# Sensor_Board.net
KiCad netlist of a schematic drawn in Altium Designer
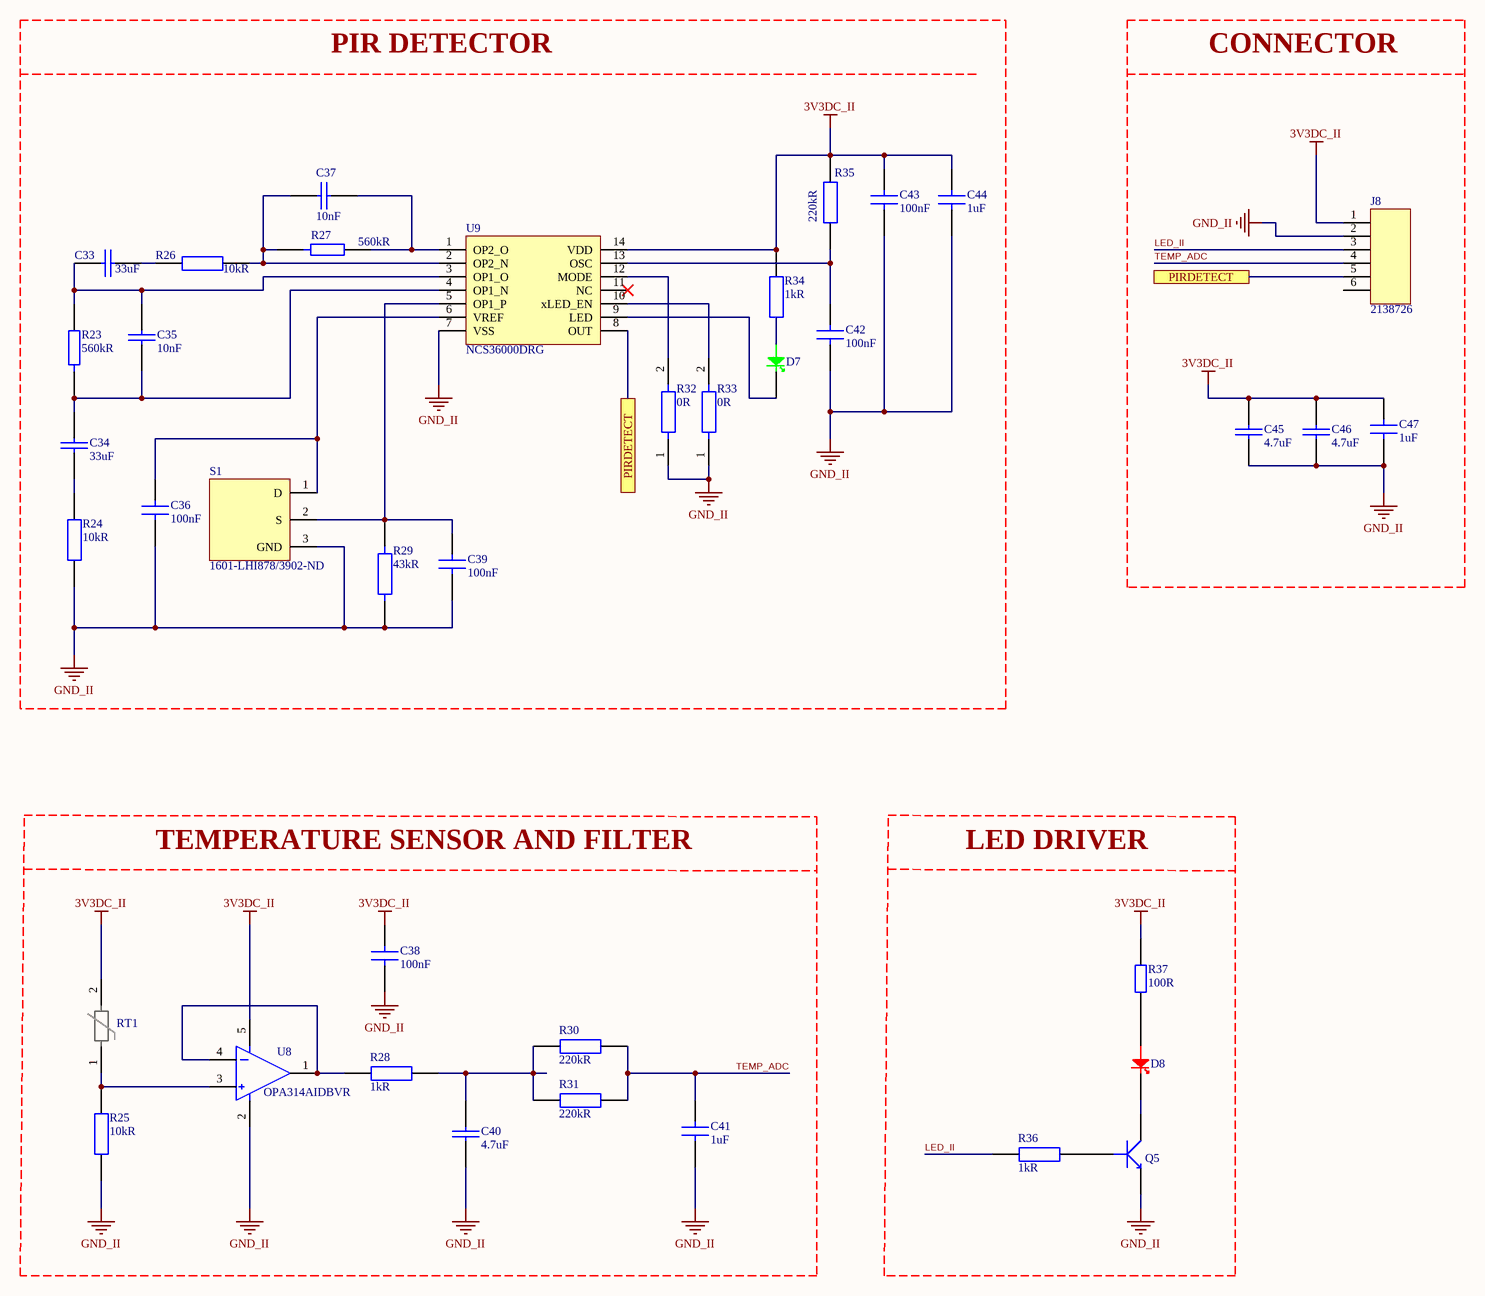
[diagram p0: Sensor Board.SchDoc]

(export (version "E")
  (design (tool "Eeschema 10.0.6"))
  (components
    (comp (ref "C33")
      (value "C3216X5R1E336M160AC")
      (footprint "CAP_1206")
      (description "Cap Ceramic 33uF 25V X5R 20% SMD 1206 85C T/R")
      (fields
        (field (name "MANUFACTURER") "TDK")
        (field (name "TOLERANCE") "20%")
        (field (name "CAPACITANCE") "33uF")
      )
      (libsource (lib "SecurityBoard") (part "CAP CER 33uF 1206"))
    )
    (comp (ref "C34")
      (value "C3216X5R1E336M160AC")
      (footprint "CAP_1206")
      (description "Cap Ceramic 33uF 25V X5R 20% SMD 1206 85C T/R")
      (fields
        (field (name "MANUFACTURER") "TDK")
        (field (name "TOLERANCE") "20%")
        (field (name "CAPACITANCE") "33uF")
      )
      (libsource (lib "SecurityBoard") (part "CAP CER 33uF 1206"))
    )
    (comp (ref "C35")
      (value "0603B103K160CT")
      (footprint "cap_0603")
      (fields
        (field (name "MANUFACTURER") "Walsin Technologies")
        (field (name "TOLERANCE") "10%")
        (field (name "CAPACITANCE") "10nF")
      )
      (libsource (lib "SecurityBoard") (part "CAP CER 10nF 0603"))
    )
    (comp (ref "C36")
      (value "C0603X104K4RACTU")
      (footprint "cap_0603")
      (description "CAP CER 0.1UF 16V X7R 0603")
      (fields
        (field (name "MANUFACTURER") "KEMET")
        (field (name "TOLERANCE") "10%")
        (field (name "CAPACITANCE") "100nF")
        (field (name "DESIGNEDBY") "ENES")
      )
      (libsource (lib "SecurityBoard") (part "CAP CER 100nF  0603"))
    )
    (comp (ref "C37")
      (value "0603B103K160CT")
      (footprint "cap_0603")
      (fields
        (field (name "MANUFACTURER") "Walsin Technologies")
        (field (name "TOLERANCE") "10%")
        (field (name "CAPACITANCE") "10nF")
      )
      (libsource (lib "SecurityBoard") (part "CAP CER 10nF 0603"))
    )
    (comp (ref "C38")
      (value "C0603X104K4RACTU")
      (footprint "cap_0603")
      (description "CAP CER 0.1UF 16V X7R 0603")
      (fields
        (field (name "MANUFACTURER") "KEMET")
        (field (name "TOLERANCE") "10%")
        (field (name "CAPACITANCE") "100nF")
        (field (name "DESIGNEDBY") "ENES")
      )
      (libsource (lib "SecurityBoard") (part "CAP CER 100nF  0603"))
    )
    (comp (ref "C39")
      (value "C0603X104K4RACTU")
      (footprint "cap_0603")
      (description "CAP CER 0.1UF 16V X7R 0603")
      (fields
        (field (name "MANUFACTURER") "KEMET")
        (field (name "TOLERANCE") "10%")
        (field (name "CAPACITANCE") "100nF")
        (field (name "DESIGNEDBY") "ENES")
      )
      (libsource (lib "SecurityBoard") (part "CAP CER 100nF  0603"))
    )
    (comp (ref "C40")
      (value "CL21A475KAQNNNE")
      (footprint "CAP_0805")
      (description "CAP CER 4.7uF %10 0805")
      (fields
        (field (name "MANUFACTURER") "Samsung")
        (field (name "TOLERANCE") "10%")
        (field (name "CAPACITANCE") "4.7uF")
      )
      (libsource (lib "SecurityBoard") (part "CAP CER 4.7uF 0805"))
    )
    (comp (ref "C41")
      (value "CL21B105KBFNNNE")
      (footprint "CAP_0805")
      (fields
        (field (name "MANUFACTURER") "Samsung")
        (field (name "TOLERANCE") "10%")
        (field (name "VOLTAGE") "50V")
        (field (name "CAPACITANCE") "1uF")
      )
      (libsource (lib "SecurityBoard") (part "CAP CER 1uF 0805"))
    )
    (comp (ref "C42")
      (value "C0603X104K4RACTU")
      (footprint "cap_0603")
      (description "CAP CER 0.1UF 16V X7R 0603")
      (fields
        (field (name "MANUFACTURER") "KEMET")
        (field (name "TOLERANCE") "10%")
        (field (name "CAPACITANCE") "100nF")
        (field (name "DESIGNEDBY") "ENES")
      )
      (libsource (lib "SecurityBoard") (part "CAP CER 100nF  0603"))
    )
    (comp (ref "C43")
      (value "C0603X104K4RACTU")
      (footprint "cap_0603")
      (description "CAP CER 0.1UF 16V X7R 0603")
      (fields
        (field (name "MANUFACTURER") "KEMET")
        (field (name "TOLERANCE") "10%")
        (field (name "CAPACITANCE") "100nF")
        (field (name "DESIGNEDBY") "ENES")
      )
      (libsource (lib "SecurityBoard") (part "CAP CER 100nF  0603"))
    )
    (comp (ref "C44")
      (value "CL21B105KBFNNNE")
      (footprint "CAP_0805")
      (fields
        (field (name "MANUFACTURER") "Samsung")
        (field (name "TOLERANCE") "10%")
        (field (name "VOLTAGE") "50V")
        (field (name "CAPACITANCE") "1uF")
      )
      (libsource (lib "SecurityBoard") (part "CAP CER 1uF 0805"))
    )
    (comp (ref "C45")
      (value "CL21A475KAQNNNE")
      (footprint "CAP_0805")
      (description "CAP CER 4.7uF %10 0805")
      (fields
        (field (name "MANUFACTURER") "Samsung")
        (field (name "TOLERANCE") "10%")
        (field (name "CAPACITANCE") "4.7uF")
      )
      (libsource (lib "SecurityBoard") (part "CAP CER 4.7uF 0805"))
    )
    (comp (ref "C46")
      (value "CL21A475KAQNNNE")
      (footprint "CAP_0805")
      (description "CAP CER 4.7uF %10 0805")
      (fields
        (field (name "MANUFACTURER") "Samsung")
        (field (name "TOLERANCE") "10%")
        (field (name "CAPACITANCE") "4.7uF")
      )
      (libsource (lib "SecurityBoard") (part "CAP CER 4.7uF 0805"))
    )
    (comp (ref "C47")
      (value "CL21B105KBFNNNE")
      (footprint "CAP_0805")
      (fields
        (field (name "MANUFACTURER") "Samsung")
        (field (name "TOLERANCE") "10%")
        (field (name "VOLTAGE") "50V")
        (field (name "CAPACITANCE") "1uF")
      )
      (libsource (lib "SecurityBoard") (part "CAP CER 1uF 0805"))
    )
    (comp (ref "D7")
      (value "APT1608ZGCK")
      (footprint "LED_GR_0805")
      (description "Green 1.6 x 0.8 mm 120° 350 mcd Clear 3.3 V Surface Mount Chip LED Lamp")
      (fields (field (name "MANUFACTURER") "Kingbright"))
      (libsource (lib "SecurityBoard") (part "LED GREEN 0805"))
    )
    (comp (ref "D8")
      (value "LTST-C171EKT")
      (footprint "LED_RED_0805")
      (description "LED RED CLEAR 0805 SMD")
      (fields (field (name "MANUFACTURER") "Vishay Lite-On"))
      (libsource (lib "SecurityBoard") (part "LED RED 0805"))
    )
    (comp (ref "J8")
      (value "64800611622")
      (footprint "64800611622")
      (fields
        (field (name "MANUFACTURER") "Wurth Electronics")
        (field (name "SUPPLIER PART NUMBER 1") "2138726")
      )
      (libsource (lib "SecurityBoard") (part "64800611622_conn_6pin"))
    )
    (comp (ref "Q5")
      (value "MMBT3904-7-F")
      (footprint "MMBT3904-7-F")
      (description "Transistor General Purpose BJT NPN 40 Volt 0.2A Automotive 3-Pin SOT-23")
      (fields (field (name "MANUFACTURER") "Diodes Zetex"))
      (libsource (lib "SecurityBoard") (part "MMBT3904-7-F"))
    )
    (comp (ref "R23")
      (value "RC0603JR-07560KL")
      (footprint "res_0603")
      (description "RES SMD 560K OHM 5% 1/10W 0603")
      (fields
        (field (name "MANUFACTURER") "Yageo")
        (field (name "TOLERANCE") "5%")
        (field (name "RESISTANCE") "560kR")
      )
      (libsource (lib "SecurityBoard") (part "RES 560K OHM 0603"))
    )
    (comp (ref "R24")
      (value "RC0603FR-0710KL")
      (footprint "res_0603")
      (description "Res General Purpose Thick Film 0603 10K Ohm 1% 1/10W ±100ppm/°C Molded SMD Paper T/R")
      (fields
        (field (name "MANUFACTURER") "Yageo")
        (field (name "TOLERANCE") "1%")
        (field (name "RESISTANCE") "10kR")
      )
      (libsource (lib "SecurityBoard") (part "RES 10K OHM 0603"))
    )
    (comp (ref "R25")
      (value "RC0603FR-0710KL")
      (footprint "res_0603")
      (description "Res General Purpose Thick Film 0603 10K Ohm 1% 1/10W ±100ppm/°C Molded SMD Paper T/R")
      (fields
        (field (name "MANUFACTURER") "Yageo")
        (field (name "TOLERANCE") "1%")
        (field (name "RESISTANCE") "10kR")
      )
      (libsource (lib "SecurityBoard") (part "RES 10K OHM 0603"))
    )
    (comp (ref "R26")
      (value "RC0603FR-0710KL")
      (footprint "res_0603")
      (description "Res General Purpose Thick Film 0603 10K Ohm 1% 1/10W ±100ppm/°C Molded SMD Paper T/R")
      (fields
        (field (name "MANUFACTURER") "Yageo")
        (field (name "TOLERANCE") "1%")
        (field (name "RESISTANCE") "10kR")
      )
      (libsource (lib "SecurityBoard") (part "RES 10K OHM 0603"))
    )
    (comp (ref "R27")
      (value "RC0603JR-07560KL")
      (footprint "res_0603")
      (description "RES SMD 560K OHM 5% 1/10W 0603")
      (fields
        (field (name "MANUFACTURER") "Yageo")
        (field (name "TOLERANCE") "5%")
        (field (name "RESISTANCE") "560kR")
      )
      (libsource (lib "SecurityBoard") (part "RES 560K OHM 0603"))
    )
    (comp (ref "R28")
      (value "AC0603FR-071KL")
      (footprint "res_0603")
      (description "Res Thick Film 0603 1K Ohm 1% 0.1W(1/10W) ±100ppm/C Epoxy Pad SMD Automotive T/R")
      (fields
        (field (name "MANUFACTURER") "Yageo")
        (field (name "TOLERANCE") "1%")
        (field (name "RESISTANCE") "1kR")
      )
      (libsource (lib "SecurityBoard") (part "RES 1K OHM 0603"))
    )
    (comp (ref "R29")
      (value "RC0603DR-0743KL")
      (footprint "res_0603")
      (description "General Purpose Chip Resistor Thick Film 0603 43kOhm 0.5% Paper T/R")
      (fields
        (field (name "MANUFACTURER") "Yageo")
        (field (name "TOLERANCE") "0.5%")
        (field (name "RESISTANCE") "43kR")
      )
      (libsource (lib "SecurityBoard") (part "RES 43K OHM 0603"))
    )
    (comp (ref "R30")
      (value "RT0603BRD07220KL")
      (footprint "res_0603")
      (description "Thin Film Resistors - SMD 1/10W 220K ohm .1% 25ppm")
      (fields
        (field (name "MANUFACTURER") "Yageo")
        (field (name "TOLERANCE") "0.1%")
        (field (name "RESISTANCE") "220kR")
      )
      (libsource (lib "SecurityBoard") (part "RES 220K OHM 0603"))
    )
    (comp (ref "R31")
      (value "RT0603BRD07220KL")
      (footprint "res_0603")
      (description "Thin Film Resistors - SMD 1/10W 220K ohm .1% 25ppm")
      (fields
        (field (name "MANUFACTURER") "Yageo")
        (field (name "TOLERANCE") "0.1%")
        (field (name "RESISTANCE") "220kR")
      )
      (libsource (lib "SecurityBoard") (part "RES 220K OHM 0603"))
    )
    (comp (ref "R32")
      (value "RC0603JR-070RL")
      (footprint "res_0603")
      (description "RES SMD 0 OHM JUMPER 1/10W 0603")
      (fields
        (field (name "MANUFACTURER") "Yageo")
        (field (name "TOLERANCE") "1%")
        (field (name "RESISTANCE") "0R")
      )
      (libsource (lib "SecurityBoard") (part "RES 0 OHM 0603"))
    )
    (comp (ref "R33")
      (value "RC0603JR-070RL")
      (footprint "res_0603")
      (description "RES SMD 0 OHM JUMPER 1/10W 0603")
      (fields
        (field (name "MANUFACTURER") "Yageo")
        (field (name "TOLERANCE") "1%")
        (field (name "RESISTANCE") "0R")
      )
      (libsource (lib "SecurityBoard") (part "RES 0 OHM 0603"))
    )
    (comp (ref "R34")
      (value "AC0603FR-071KL")
      (footprint "res_0603")
      (description "Res Thick Film 0603 1K Ohm 1% 0.1W(1/10W) ±100ppm/C Epoxy Pad SMD Automotive T/R")
      (fields
        (field (name "MANUFACTURER") "Yageo")
        (field (name "TOLERANCE") "1%")
        (field (name "RESISTANCE") "1kR")
      )
      (libsource (lib "SecurityBoard") (part "RES 1K OHM 0603"))
    )
    (comp (ref "R35")
      (value "RT0603BRD07220KL")
      (footprint "res_0603")
      (description "Thin Film Resistors - SMD 1/10W 220K ohm .1% 25ppm")
      (fields
        (field (name "MANUFACTURER") "Yageo")
        (field (name "TOLERANCE") "0.1%")
        (field (name "RESISTANCE") "220kR")
      )
      (libsource (lib "SecurityBoard") (part "RES 220K OHM 0603"))
    )
    (comp (ref "R36")
      (value "AC0603FR-071KL")
      (footprint "res_0603")
      (description "Res Thick Film 0603 1K Ohm 1% 0.1W(1/10W) ±100ppm/C Epoxy Pad SMD Automotive T/R")
      (fields
        (field (name "MANUFACTURER") "Yageo")
        (field (name "TOLERANCE") "1%")
        (field (name "RESISTANCE") "1kR")
      )
      (libsource (lib "SecurityBoard") (part "RES 1K OHM 0603"))
    )
    (comp (ref "R37")
      (value "RE0603DRE07100RL")
      (footprint "res_0603")
      (description "Chip Resistor Precision Grade Thick Film 0603 100Ohm 0.5% Paper T/R")
      (fields
        (field (name "MANUFACTURER") "Yageo")
        (field (name "TOLERANCE") "0.5%")
        (field (name "RESISTANCE") "100R")
      )
      (libsource (lib "SecurityBoard") (part "RES 100 OHM 0603"))
    )
    (comp (ref "RT1")
      (value "TFPT1206L1002FM")
      (footprint "TFPT1206L1002FM")
      (description "Thermistor PTC 10K Ohm 1% 2-Pin 1206 Surface Mount Solder Pad T/R Automotive")
      (fields (field (name "MANUFACTURER") "Vishay Dale") (field (name "TOLERANCE") "1%"))
      (libsource (lib "SecurityBoard") (part "TFPT1206L1002FM"))
    )
    (comp (ref "S1")
      (value "1601-LHI878/3902-ND")
      (footprint "LHI 878/3902")
      (description "Sensor Pyro Detector Dual Motion")
      (fields
        (field (name "MANUFACTURER") "Excelitas Technology")
        (field (name "MANUFACTURER PART NUMBER") "LHI 878/3902")
        (field (name "DESIGNEDBY") "ENES")
      )
      (libsource (lib "SecurityBoard") (part "LHI 878/3902"))
    )
    (comp (ref "U8")
      (value "OPA314AIDBVR")
      (footprint "SOT23-5")
      (description "Op Amp OPA314AIDBVR")
      (fields (field (name "MANUFACTURER") "Texas Instruments"))
      (libsource (lib "SecurityBoard") (part "OPA314"))
    )
    (comp (ref "U9")
      (value "NCS36000DRG")
      (footprint "SOIC14")
      (description "Low Noise Amplifiers and LDO Regulator 14-Pin SOIC N T/R")
      (fields (field (name "MANUFACTURER") "ON Semiconductor"))
      (libsource (lib "SecurityBoard") (part "NCS36000DRG"))
    )
  )
  (nets
    (net (code "1") (name "/LED_II") (class "Default")
      (node (ref "J8") (pin "3") (pinfunction "3_3") (pintype "passive"))
      (node (ref "R36") (pin "1") (pinfunction "1_1") (pintype "passive"))
    )
    (net (code "2") (name "/PIRDETECT") (class "Default")
      (node (ref "J8") (pin "5") (pinfunction "5_5") (pintype "passive"))
      (node (ref "U9") (pin "8") (pinfunction "OUT_8") (pintype "passive"))
    )
    (net (code "3") (name "/TEMP_ADC") (class "Default")
      (node (ref "C41") (pin "2") (pinfunction "2_2") (pintype "passive"))
      (node (ref "J8") (pin "4") (pinfunction "4_4") (pintype "passive"))
      (node (ref "R30") (pin "2") (pinfunction "2_2") (pintype "passive"))
      (node (ref "R31") (pin "2") (pinfunction "2_2") (pintype "passive"))
    )
    (net (code "4") (name "3V3DC_II") (class "Default")
      (node (ref "C38") (pin "2") (pinfunction "2_2") (pintype "passive"))
      (node (ref "C43") (pin "2") (pinfunction "2_2") (pintype "passive"))
      (node (ref "C44") (pin "2") (pinfunction "2_2") (pintype "passive"))
      (node (ref "C45") (pin "2") (pinfunction "2_2") (pintype "passive"))
      (node (ref "C46") (pin "2") (pinfunction "2_2") (pintype "passive"))
      (node (ref "C47") (pin "2") (pinfunction "2_2") (pintype "passive"))
      (node (ref "J8") (pin "1") (pinfunction "1_1") (pintype "passive"))
      (node (ref "R34") (pin "2") (pinfunction "2_2") (pintype "passive"))
      (node (ref "R35") (pin "2") (pinfunction "2_2") (pintype "passive"))
      (node (ref "R37") (pin "2") (pinfunction "2_2") (pintype "passive"))
      (node (ref "RT1") (pin "2") (pinfunction "2_2") (pintype "passive"))
      (node (ref "U8") (pin "5") (pinfunction "5_5") (pintype "passive"))
      (node (ref "U9") (pin "14") (pinfunction "VDD_14") (pintype "passive"))
    )
    (net (code "5") (name "GND_II") (class "Default")
      (node (ref "C36") (pin "1") (pinfunction "1_1") (pintype "passive"))
      (node (ref "C38") (pin "1") (pinfunction "1_1") (pintype "passive"))
      (node (ref "C39") (pin "1") (pinfunction "1_1") (pintype "passive"))
      (node (ref "C40") (pin "1") (pinfunction "1_1") (pintype "passive"))
      (node (ref "C41") (pin "1") (pinfunction "1_1") (pintype "passive"))
      (node (ref "C42") (pin "1") (pinfunction "1_1") (pintype "passive"))
      (node (ref "C43") (pin "1") (pinfunction "1_1") (pintype "passive"))
      (node (ref "C44") (pin "1") (pinfunction "1_1") (pintype "passive"))
      (node (ref "C45") (pin "1") (pinfunction "1_1") (pintype "passive"))
      (node (ref "C46") (pin "1") (pinfunction "1_1") (pintype "passive"))
      (node (ref "C47") (pin "1") (pinfunction "1_1") (pintype "passive"))
      (node (ref "J8") (pin "2") (pinfunction "2_2") (pintype "passive"))
      (node (ref "Q5") (pin "E") (pinfunction "E_E") (pintype "passive"))
      (node (ref "R24") (pin "1") (pinfunction "1_1") (pintype "passive"))
      (node (ref "R25") (pin "1") (pinfunction "1_1") (pintype "passive"))
      (node (ref "R29") (pin "1") (pinfunction "_1_1") (pintype "passive"))
      (node (ref "R32") (pin "1") (pinfunction "_1_1") (pintype "passive"))
      (node (ref "R33") (pin "1") (pinfunction "_1_1") (pintype "passive"))
      (node (ref "S1") (pin "3") (pinfunction "GND_3") (pintype "passive"))
      (node (ref "U8") (pin "2") (pinfunction "2_2") (pintype "passive"))
      (node (ref "U9") (pin "7") (pinfunction "VSS_7") (pintype "passive"))
    )
    (net (code "6") (name "Net-(C33-Pad2)") (class "Default")
      (node (ref "C33") (pin "2") (pinfunction "2_2") (pintype "passive"))
      (node (ref "R26") (pin "1") (pinfunction "1_1") (pintype "passive"))
    )
    (net (code "7") (name "Net-(C34-Pad1)") (class "Default")
      (node (ref "C34") (pin "1") (pinfunction "1_1") (pintype "passive"))
      (node (ref "R24") (pin "2") (pinfunction "2_2") (pintype "passive"))
    )
    (net (code "8") (name "Net-(C40-Pad2)") (class "Default")
      (node (ref "C40") (pin "2") (pinfunction "2_2") (pintype "passive"))
      (node (ref "R28") (pin "2") (pinfunction "2_2") (pintype "passive"))
      (node (ref "R30") (pin "1") (pinfunction "1_1") (pintype "passive"))
      (node (ref "R31") (pin "1") (pinfunction "1_1") (pintype "passive"))
    )
    (net (code "9") (name "Net-(D7-Pad1)") (class "Default")
      (node (ref "D7") (pin "1") (pinfunction "1_1") (pintype "passive"))
      (node (ref "R34") (pin "1") (pinfunction "1_1") (pintype "passive"))
    )
    (net (code "10") (name "Net-(D8-Pad1)") (class "Default")
      (node (ref "D8") (pin "1") (pinfunction "1_1") (pintype "passive"))
      (node (ref "R37") (pin "1") (pinfunction "1_1") (pintype "passive"))
    )
    (net (code "11") (name "Net-(D8-Pad2)") (class "Default")
      (node (ref "D8") (pin "2") (pinfunction "2_2") (pintype "passive"))
      (node (ref "Q5") (pin "C") (pinfunction "C_C") (pintype "passive"))
    )
    (net (code "12") (name "Net-(Q5-PadB)") (class "Default")
      (node (ref "Q5") (pin "B") (pinfunction "B_B") (pintype "passive"))
      (node (ref "R36") (pin "2") (pinfunction "2_2") (pintype "passive"))
    )
    (net (code "13") (name "Net-(R23-_1)") (class "Default")
      (node (ref "C34") (pin "2") (pinfunction "2_2") (pintype "passive"))
      (node (ref "C35") (pin "2") (pinfunction "2_2") (pintype "passive"))
      (node (ref "R23") (pin "1") (pinfunction "_1_1") (pintype "passive"))
      (node (ref "U9") (pin "4") (pinfunction "OP1_N_4") (pintype "passive"))
    )
    (net (code "14") (name "Net-(R23-_2)") (class "Default")
      (node (ref "C33") (pin "1") (pinfunction "1_1") (pintype "passive"))
      (node (ref "C35") (pin "1") (pinfunction "1_1") (pintype "passive"))
      (node (ref "R23") (pin "2") (pinfunction "_2_2") (pintype "passive"))
      (node (ref "U9") (pin "3") (pinfunction "OP1_O_3") (pintype "passive"))
    )
    (net (code "15") (name "Net-(R25-Pad2)") (class "Default")
      (node (ref "R25") (pin "2") (pinfunction "2_2") (pintype "passive"))
      (node (ref "RT1") (pin "1") (pinfunction "1_1") (pintype "passive"))
      (node (ref "U8") (pin "3") (pinfunction "3_3") (pintype "passive"))
    )
    (net (code "16") (name "Net-(R27-_1)") (class "Default")
      (node (ref "C37") (pin "1") (pinfunction "1_1") (pintype "passive"))
      (node (ref "R26") (pin "2") (pinfunction "2_2") (pintype "passive"))
      (node (ref "R27") (pin "1") (pinfunction "_1_1") (pintype "passive"))
      (node (ref "U9") (pin "2") (pinfunction "OP2_N_2") (pintype "passive"))
    )
    (net (code "17") (name "Net-(R27-_2)") (class "Default")
      (node (ref "C37") (pin "2") (pinfunction "2_2") (pintype "passive"))
      (node (ref "R27") (pin "2") (pinfunction "_2_2") (pintype "passive"))
      (node (ref "U9") (pin "1") (pinfunction "OP2_O_1") (pintype "passive"))
    )
    (net (code "18") (name "Net-(R28-Pad1)") (class "Default")
      (node (ref "R28") (pin "1") (pinfunction "1_1") (pintype "passive"))
      (node (ref "U8") (pin "1") (pinfunction "1_1") (pintype "passive"))
      (node (ref "U8") (pin "4") (pinfunction "4_4") (pintype "passive"))
    )
    (net (code "19") (name "Net-(R29-_2)") (class "Default")
      (node (ref "C39") (pin "2") (pinfunction "2_2") (pintype "passive"))
      (node (ref "R29") (pin "2") (pinfunction "_2_2") (pintype "passive"))
      (node (ref "S1") (pin "2") (pinfunction "S_2") (pintype "passive"))
      (node (ref "U9") (pin "5") (pinfunction "OP1_P_5") (pintype "passive"))
    )
    (net (code "20") (name "Net-(R32-_2)") (class "Default")
      (node (ref "R32") (pin "2") (pinfunction "_2_2") (pintype "passive"))
      (node (ref "U9") (pin "12") (pinfunction "MODE_12") (pintype "passive"))
    )
    (net (code "21") (name "Net-(R33-_2)") (class "Default")
      (node (ref "R33") (pin "2") (pinfunction "_2_2") (pintype "passive"))
      (node (ref "U9") (pin "10") (pinfunction "xLED_EN_10") (pintype "passive"))
    )
    (net (code "22") (name "Net-(S1-D)") (class "Default")
      (node (ref "C36") (pin "2") (pinfunction "2_2") (pintype "passive"))
      (node (ref "S1") (pin "1") (pinfunction "D_1") (pintype "passive"))
      (node (ref "U9") (pin "6") (pinfunction "VREF_6") (pintype "passive"))
    )
    (net (code "23") (name "Net-(U9-LED)") (class "Default")
      (node (ref "D7") (pin "2") (pinfunction "2_2") (pintype "passive"))
      (node (ref "U9") (pin "9") (pinfunction "LED_9") (pintype "passive"))
    )
    (net (code "24") (name "Net-(U9-OSC)") (class "Default")
      (node (ref "C42") (pin "2") (pinfunction "2_2") (pintype "passive"))
      (node (ref "R35") (pin "1") (pinfunction "1_1") (pintype "passive"))
      (node (ref "U9") (pin "13") (pinfunction "OSC_13") (pintype "passive"))
    )
    (net (code "25") (name "unconnected-(J8-Pad6)") (class "Default")
      (node (ref "J8") (pin "6") (pinfunction "6_6") (pintype "passive"))
    )
    (net (code "26") (name "unconnected-(U9-NC-Pad11)") (class "Default")
      (node (ref "U9") (pin "11") (pinfunction "NC_11") (pintype "passive+no_connect"))
    )
  )
)
